# MB1137.net
KiCad netlist of a schematic drawn in Altium Designer
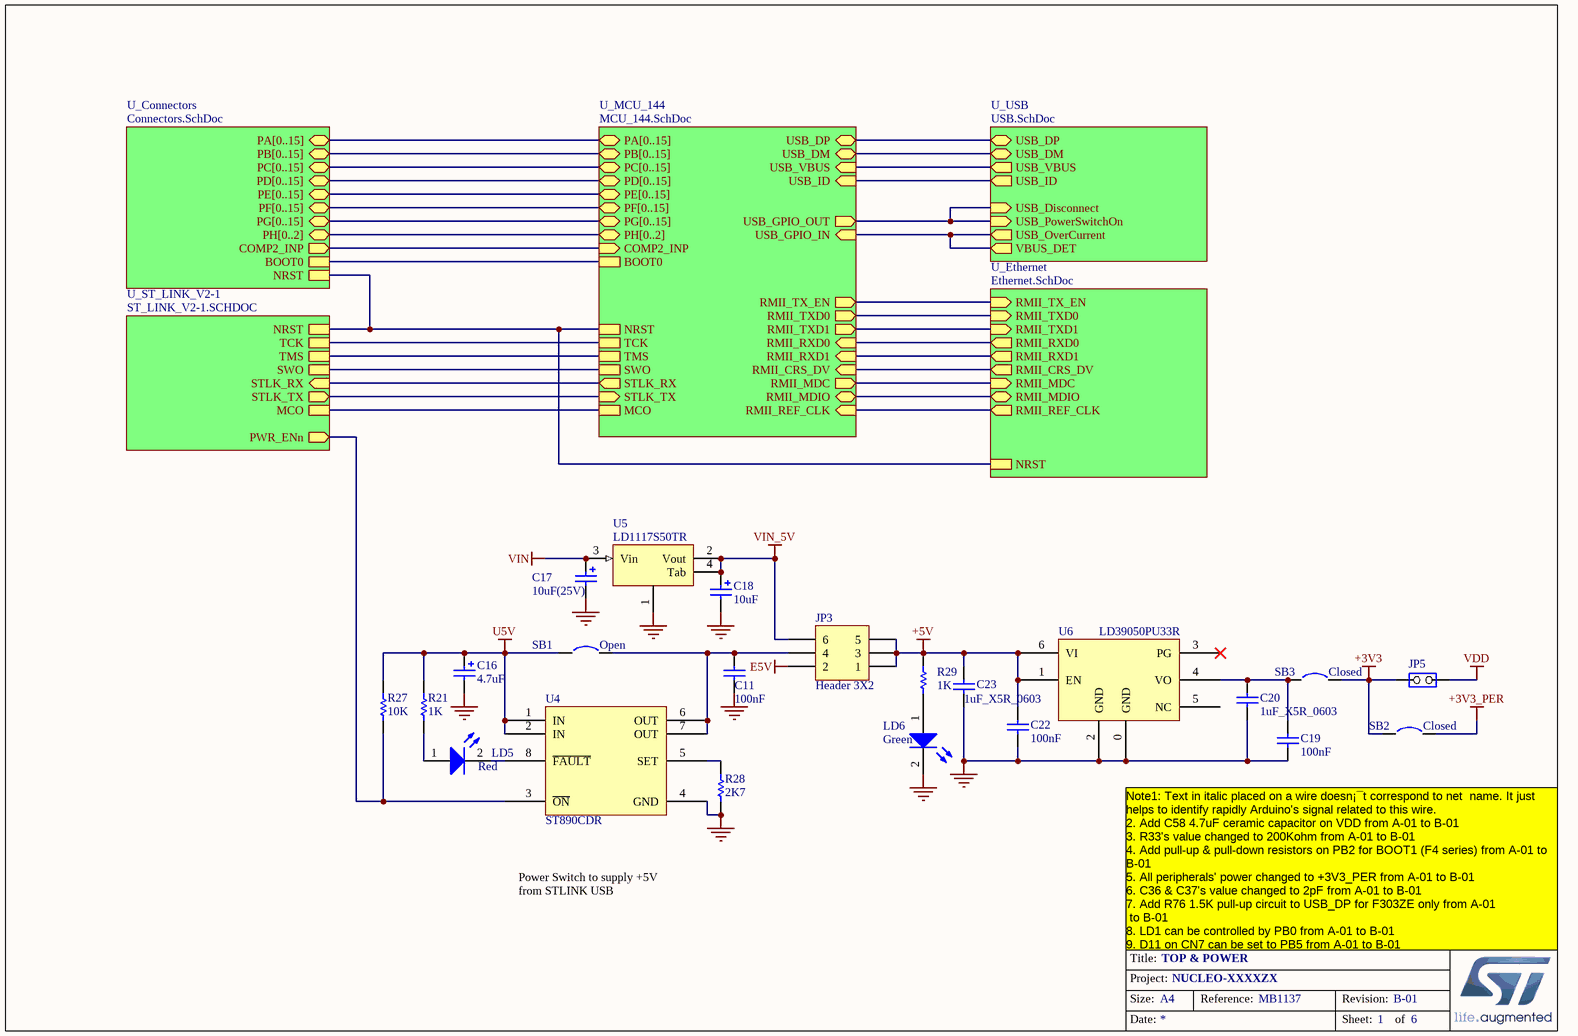
[diagram p0: MB1137.SchDoc]

(export (version "E")
  (design (tool "Eeschema 10.0.6"))
  (components
    (comp (ref "C11")
      (value "100nF")
      (footprint "0603C")
      (description "Capacitor 0402 / 0603 / 0805")
      (libsource (lib "MCD_TOOLS") (part "Capacitor_ST"))
    )
    (comp (ref "C16")
      (value "4.7uF")
      (footprint "TAN-A")
      (description "Polarized Capacitor (Radial)")
      (fields (field (name "PUBLISHER") "Altium Limited"))
      (libsource (lib "*") (part "Cap Pol1"))
    )
    (comp (ref "C17")
      (value "10uF(25V)")
      (footprint "TAN-B")
      (description "Polarized Capacitor (Radial)")
      (fields (field (name "PUBLISHER") "Altium Limited"))
      (libsource (lib "Miscellaneous Devices") (part "Cap Pol1"))
    )
    (comp (ref "C18")
      (value "10uF")
      (footprint "TAN-A")
      (description "Polarized Capacitor (Radial)")
      (fields (field (name "PUBLISHER") "Altium Limited"))
      (libsource (lib "Miscellaneous Devices") (part "Cap Pol1"))
    )
    (comp (ref "C19")
      (value "100nF")
      (footprint "0603C")
      (description "Capacitor 0402 / 0603 / 0805")
      (libsource (lib "MCD_TOOLS") (part "Capacitor_ST"))
    )
    (comp (ref "C20")
      (value "1uF_X5R_0603")
      (footprint "0603C")
      (description "0603  X5R 1µF")
      (fields (field (name "TOLERANCE") "10%"))
      (libsource (lib "MB963_1") (part "CAP SMD 0603  X5R 1µF 25V 10%"))
    )
    (comp (ref "C22")
      (value "100nF")
      (footprint "0603C")
      (description "Capacitor 0402 / 0603 / 0805")
      (libsource (lib "MCD_TOOLS") (part "Capacitor_ST"))
    )
    (comp (ref "C23")
      (value "1uF_X5R_0603")
      (footprint "0603C")
      (description "0603  X5R 1µF")
      (fields (field (name "TOLERANCE") "10%"))
      (libsource (lib "MB963_1") (part "CAP SMD 0603  X5R 1µF 25V 10%"))
    )
    (comp (ref "JP3")
      (value "Header 3X2")
      (footprint "HDR_3x2_2R54_V_M")
      (description "Header, 3-Pin, Dual row")
      (fields (field (name "PUBLISHER") "Altium Limited"))
      (libsource (lib "Miscellaneous Connectors") (part "Header 3X2"))
    )
    (comp (ref "JP5") (value "~") (footprint "HDR_1x2_2R54_V_M_S") (libsource (lib "*") (part "JP2")))
    (comp (ref "LD5")
      (value "Red")
      (footprint "0603D-R")
      (description "Typical RED, GREEN, YELLOW, AMBER GaAs LED")
      (fields (field (name "PUBLISHER") "Altium Limited"))
      (libsource (lib "Miscellaneous Devices") (part "LED2"))
    )
    (comp (ref "LD6")
      (value "Green")
      (footprint "0603D-G")
      (description "Typical RED, GREEN, YELLOW, AMBER GaAs LED")
      (fields (field (name "PUBLISHER") "Altium Limited"))
      (libsource (lib "") (part "LED2_1"))
    )
    (comp (ref "R21")
      (value "1K")
      (footprint "0603R")
      (description "Resistor")
      (fields (field (name "PUBLISHER") "Altium Limited"))
      (libsource (lib "*") (part "Res1"))
    )
    (comp (ref "R27")
      (value "10K")
      (footprint "STM-SMEE:0603R")
      (description "Resistor 0402 / 0603 / 0805")
      (libsource (lib "MCD_TOOLS") (part "Resistor_ST"))
    )
    (comp (ref "R28")
      (value "2K7")
      (footprint "STM-SMEE:0603R")
      (description "Resistor 0402 / 0603 / 0805")
      (libsource (lib "MCD_TOOLS") (part "Resistor_ST"))
    )
    (comp (ref "R29")
      (value "1K")
      (footprint "0603R")
      (description "Resistor 0402 / 0603 / 0805")
      (libsource (lib "MCD_TOOLS") (part "Resistor_ST"))
    )
    (comp (ref "SB1")
      (value "Open")
      (footprint "SB_0603")
      (description "Circuit Breaker")
      (fields (field (name "PUBLISHER") "Altium Limited"))
      (libsource (lib "MB1167") (part "Circuit Breaker"))
    )
    (comp (ref "SB2")
      (value "Closed")
      (footprint "SB_0603")
      (description "Circuit Breaker")
      (fields (field (name "PUBLISHER") "Altium Limited"))
      (libsource (lib "MB1167") (part "Circuit Breaker_close"))
    )
    (comp (ref "SB3")
      (value "Closed")
      (footprint "SB_0603")
      (description "Circuit Breaker")
      (fields (field (name "PUBLISHER") "Altium Limited"))
      (libsource (lib "MB1167") (part "Circuit Breaker_close"))
    )
    (comp (ref "U4")
      (value "ST890CDR")
      (footprint "SOIC8_1R27_4R9X6")
      (libsource (lib "MB1137") (part "ST890CDR"))
    )
    (comp (ref "U5") (value "LD1117S50TR") (footprint "SOT-223") (libsource (lib "MB1137") (part "LD1117")))
    (comp (ref "U6")
      (value "LD39050PU33R")
      (footprint "DFN6_0R95_3x3_TP")
      (libsource (lib "MB1137") (part "LD39050P"))
    )
  )
  (nets
    (net (code "1") (name "+3V3") (class "Default")
      (node (ref "JP5") (pin "1") (pinfunction "COMMON_1") (pintype "passive"))
      (node (ref "SB2") (pin "1") (pinfunction "1_1") (pintype "passive"))
      (node (ref "SB3") (pin "2") (pinfunction "2_2") (pintype "passive"))
    )
    (net (code "2") (name "+3V3_PER") (class "Default")
      (node (ref "SB2") (pin "2") (pinfunction "2_2") (pintype "passive"))
    )
    (net (code "3") (name "+5V") (class "Default")
      (node (ref "C22") (pin "2") (pinfunction "2_2") (pintype "passive"))
      (node (ref "C23") (pin "1") (pinfunction "1_1") (pintype "passive"))
      (node (ref "JP3") (pin "1") (pinfunction "1_1") (pintype "passive"))
      (node (ref "JP3") (pin "3") (pinfunction "3_3") (pintype "passive"))
      (node (ref "JP3") (pin "5") (pinfunction "5_5") (pintype "passive"))
      (node (ref "R29") (pin "2") (pinfunction "2_2") (pintype "passive"))
      (node (ref "U6") (pin "1") (pinfunction "EN_1") (pintype "passive"))
      (node (ref "U6") (pin "6") (pinfunction "VI_6") (pintype "passive"))
    )
    (net (code "16") (name "/PWR_ENn") (class "Default")
      (node (ref "R27") (pin "2") (pinfunction "2_2") (pintype "passive"))
      (node (ref "U4") (pin "3") (pinfunction "~{ON}_3") (pintype "passive"))
    )
    (net (code "37") (name "E5V") (class "Default")
      (node (ref "JP3") (pin "2") (pinfunction "2_2") (pintype "passive"))
    )
    (net (code "38") (name "GND") (class "Default")
      (node (ref "C11") (pin "1") (pinfunction "1_1") (pintype "passive"))
      (node (ref "C16") (pin "2") (pinfunction "2_2") (pintype "passive"))
      (node (ref "C17") (pin "2") (pinfunction "2_2") (pintype "passive"))
      (node (ref "C18") (pin "2") (pinfunction "2_2") (pintype "passive"))
      (node (ref "C19") (pin "1") (pinfunction "1_1") (pintype "passive"))
      (node (ref "C20") (pin "2") (pinfunction "2_2") (pintype "passive"))
      (node (ref "C22") (pin "1") (pinfunction "1_1") (pintype "passive"))
      (node (ref "C23") (pin "2") (pinfunction "2_2") (pintype "passive"))
      (node (ref "LD6") (pin "2") (pinfunction "K_2") (pintype "passive"))
      (node (ref "R28") (pin "1") (pinfunction "1_1") (pintype "passive"))
      (node (ref "U4") (pin "4") (pinfunction "GND_4") (pintype "passive"))
      (node (ref "U5") (pin "1") (pintype "passive"))
      (node (ref "U6") (pin "0") (pinfunction "GND_0") (pintype "passive"))
      (node (ref "U6") (pin "2") (pinfunction "GND_2") (pintype "passive"))
    )
    (net (code "39") (name "Net-(C11-Pad2)") (class "Default")
      (node (ref "C11") (pin "2") (pinfunction "2_2") (pintype "passive"))
      (node (ref "JP3") (pin "4") (pinfunction "4_4") (pintype "passive"))
      (node (ref "SB1") (pin "2") (pinfunction "2_2") (pintype "passive"))
      (node (ref "U4") (pin "6") (pinfunction "OUT_6") (pintype "passive"))
      (node (ref "U4") (pin "7") (pinfunction "OUT_7") (pintype "passive"))
    )
    (net (code "40") (name "Net-(LD5-A)") (class "Default")
      (node (ref "LD5") (pin "1") (pinfunction "A_1") (pintype "passive"))
      (node (ref "R21") (pin "2") (pinfunction "2_2") (pintype "passive"))
    )
    (net (code "41") (name "Net-(LD5-K)") (class "Default")
      (node (ref "LD5") (pin "2") (pinfunction "K_2") (pintype "passive"))
      (node (ref "U4") (pin "8") (pinfunction "~{FAULT}_8") (pintype "passive"))
    )
    (net (code "42") (name "Net-(LD6-A)") (class "Default")
      (node (ref "LD6") (pin "1") (pinfunction "A_1") (pintype "passive"))
      (node (ref "R29") (pin "1") (pinfunction "1_1") (pintype "passive"))
    )
    (net (code "43") (name "Net-(U4-SET)") (class "Default")
      (node (ref "R28") (pin "2") (pinfunction "2_2") (pintype "passive"))
      (node (ref "U4") (pin "5") (pinfunction "SET_5") (pintype "passive"))
    )
    (net (code "44") (name "Net-(U6-VO)") (class "Default")
      (node (ref "C19") (pin "2") (pinfunction "2_2") (pintype "passive"))
      (node (ref "C20") (pin "1") (pinfunction "1_1") (pintype "passive"))
      (node (ref "SB3") (pin "1") (pinfunction "1_1") (pintype "passive"))
      (node (ref "U6") (pin "4") (pinfunction "VO_4") (pintype "passive"))
    )
    (net (code "45") (name "U5V") (class "Default")
      (node (ref "C16") (pin "1") (pinfunction "1_1") (pintype "passive"))
      (node (ref "R21") (pin "1") (pinfunction "1_1") (pintype "passive"))
      (node (ref "R27") (pin "1") (pinfunction "1_1") (pintype "passive"))
      (node (ref "SB1") (pin "1") (pinfunction "1_1") (pintype "passive"))
      (node (ref "U4") (pin "1") (pinfunction "IN_1") (pintype "passive"))
      (node (ref "U4") (pin "2") (pinfunction "IN_2") (pintype "passive"))
    )
    (net (code "46") (name "VDD") (class "Default")
      (node (ref "JP5") (pin "2") (pinfunction "NO_2") (pintype "passive"))
    )
    (net (code "47") (name "VIN") (class "Default")
      (node (ref "C17") (pin "1") (pinfunction "1_1") (pintype "passive"))
      (node (ref "U5") (pin "3") (pinfunction "Vin_3") (pintype "input"))
    )
    (net (code "48") (name "VIN_5V") (class "Default")
      (node (ref "C18") (pin "1") (pinfunction "1_1") (pintype "passive"))
      (node (ref "JP3") (pin "6") (pinfunction "6_6") (pintype "passive"))
      (node (ref "U5") (pin "2") (pinfunction "Vout_2") (pintype "power_in"))
      (node (ref "U5") (pin "4") (pinfunction "Tab_4") (pintype "power_in"))
    )
    (net (code "49") (name "unconnected-(U6-NC-Pad5)") (class "Default")
      (node (ref "U6") (pin "5") (pinfunction "NC_5") (pintype "passive"))
    )
    (net (code "50") (name "unconnected-(U6-PG-Pad3)") (class "Default")
      (node (ref "U6") (pin "3") (pinfunction "PG_3") (pintype "passive+no_connect"))
    )
  )
)
